# SteinerVCF.net
KiCad netlist of a schematic drawn in EAGLE
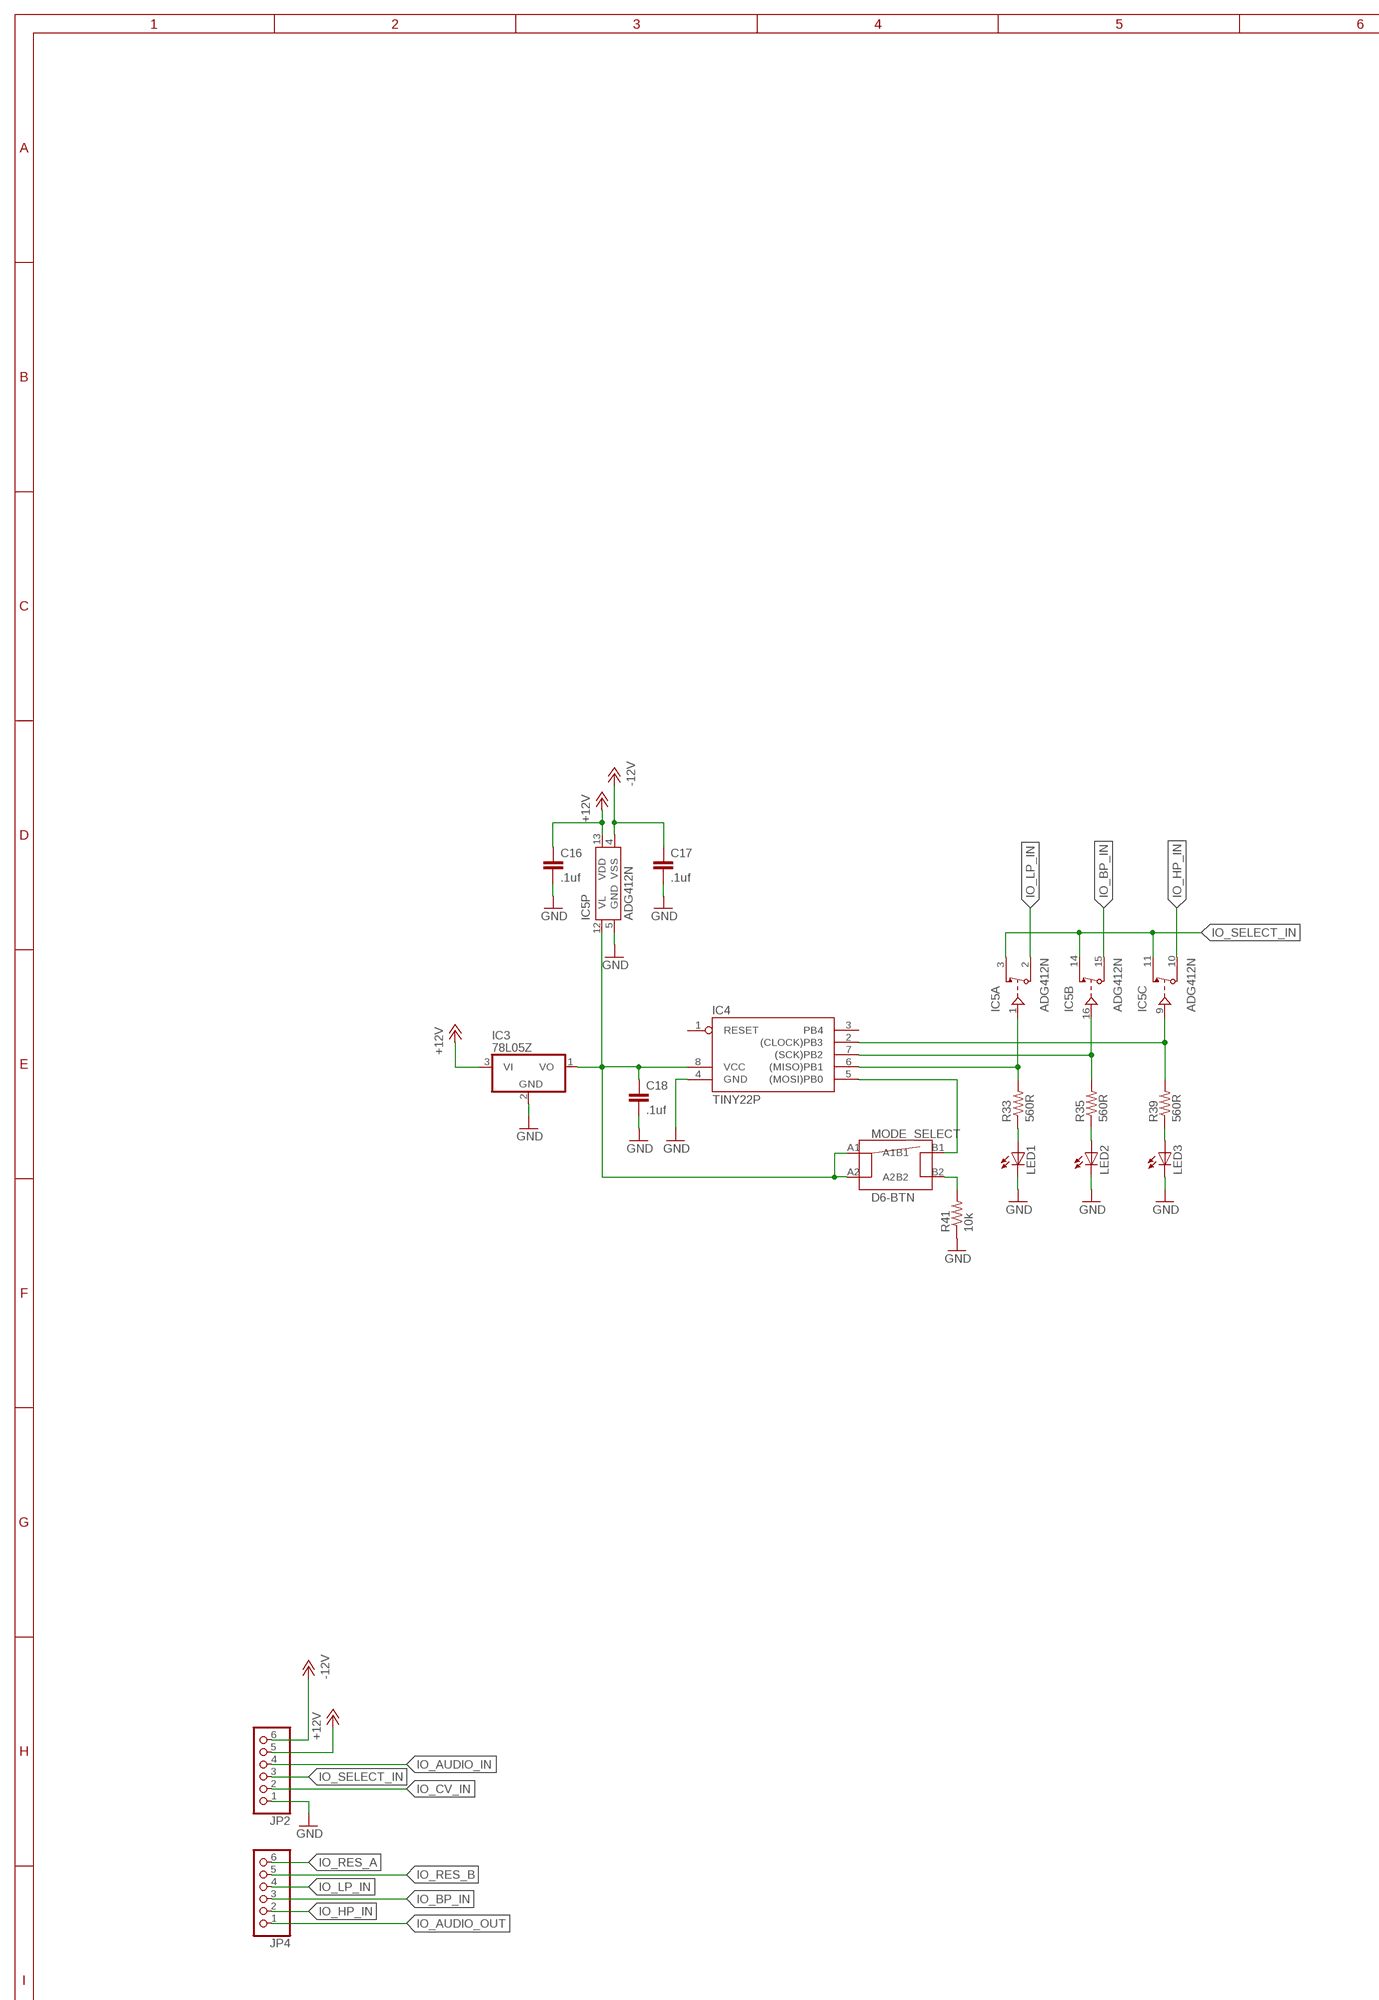
[diagram p0: schematic, sheet 1, part 1 of 2]
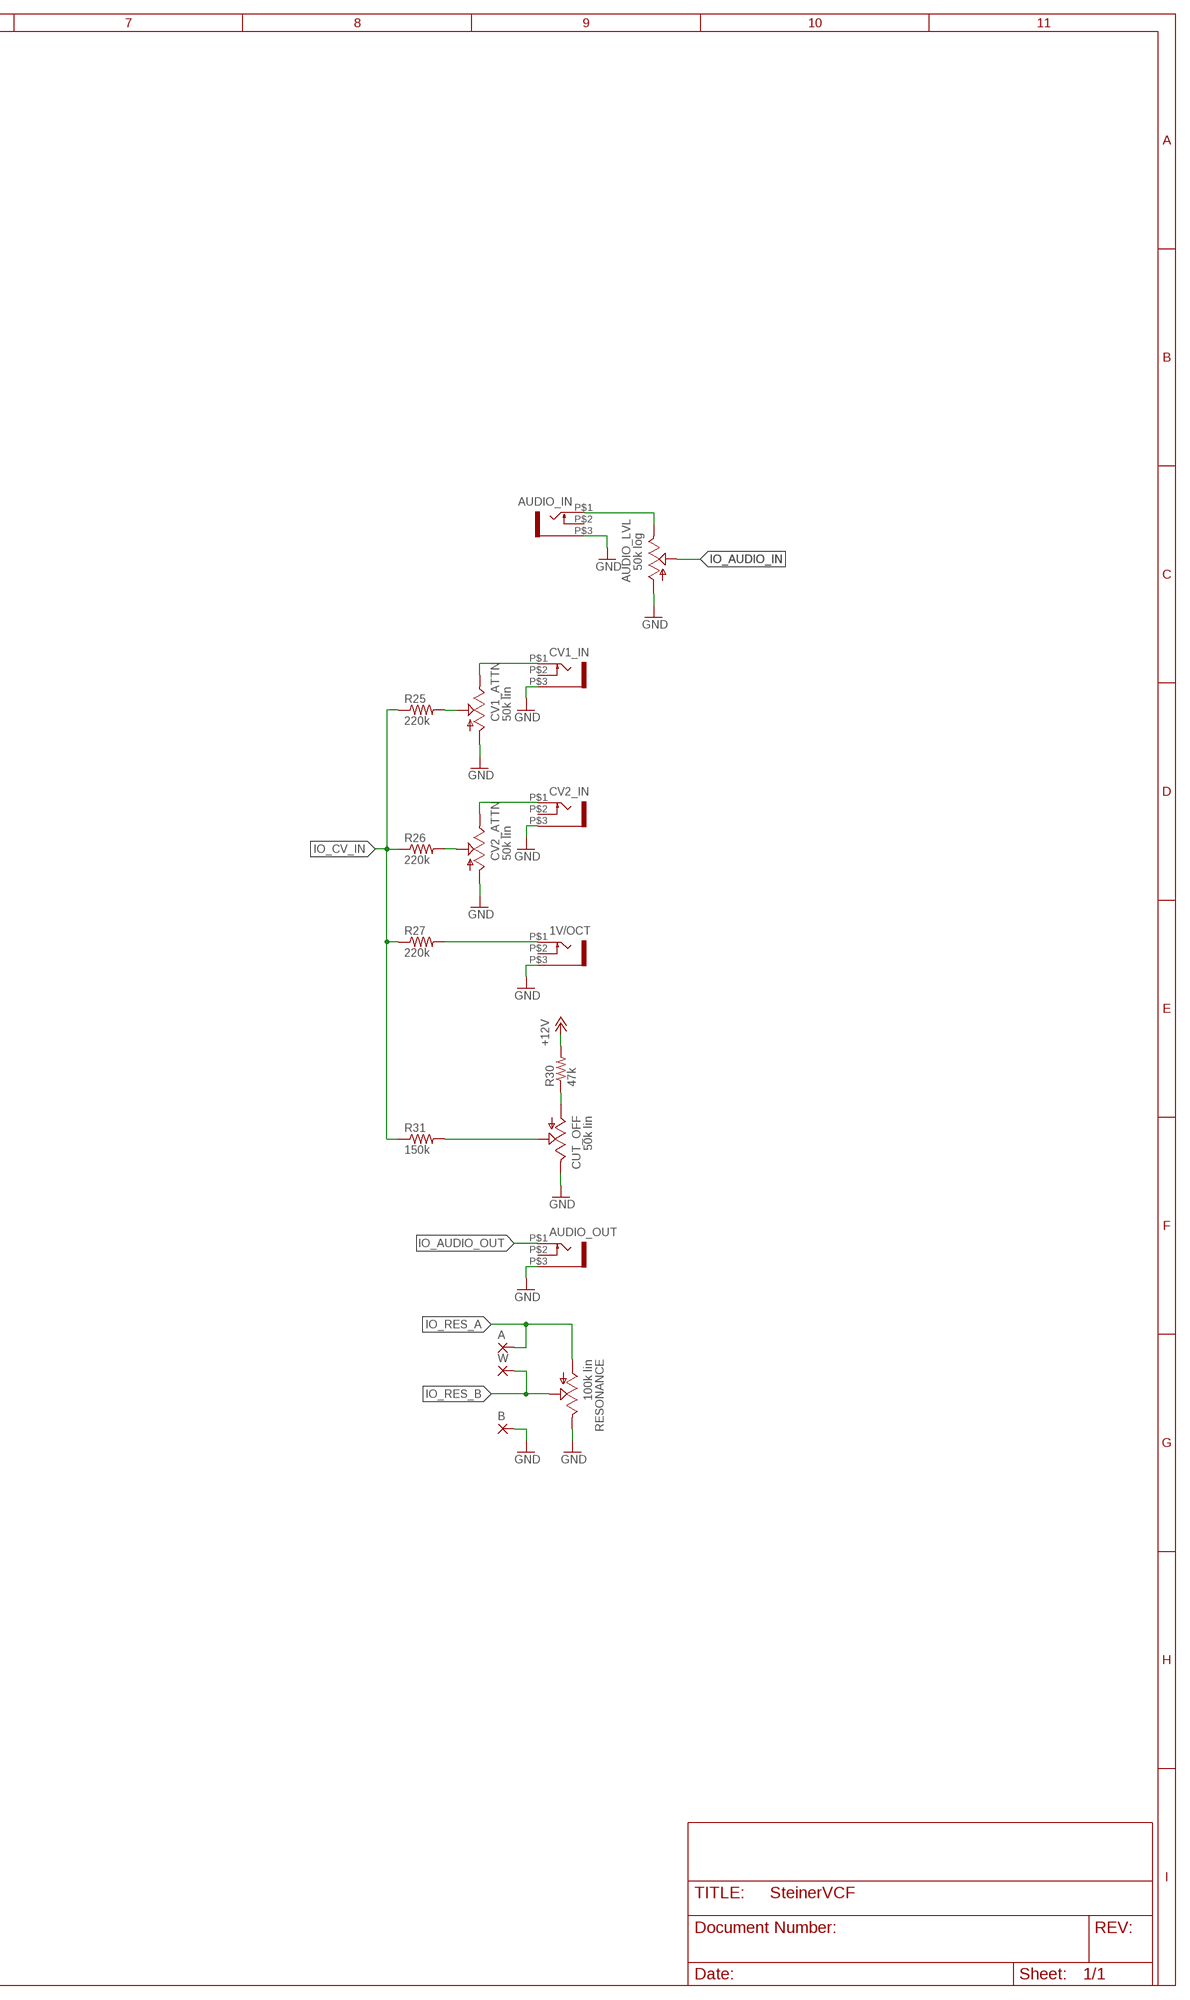
[diagram p1: schematic, sheet 1, part 2 of 2]

(export (version "E")
  (design (tool "Eeschema 10.0.6"))
  (components
    (comp (ref "1V/OCT")
      (value "WQP-PJ301M-12_JACK")
      (footprint "eagle-import:WQP-PJ301M-12_JACK")
      (libsource (lib "eagle-import") (part "WQP-PJ301M-12_JACK"))
    )
    (comp (ref "A")
      (value "2,15/1,0")
      (footprint "eagle-import:2,15_1,0")
      (libsource (lib "eagle-import") (part "2,15/1,0"))
    )
    (comp (ref "AUDIO_IN")
      (value "WQP-PJ301M-12_JACK")
      (footprint "eagle-import:WQP-PJ301M-12_JACK")
      (libsource (lib "eagle-import") (part "WQP-PJ301M-12_JACK"))
    )
    (comp (ref "AUDIO_LVL")
      (value "50k log")
      (footprint "eagle-import:EVUF")
      (libsource (lib "eagle-import") (part "ALPHA-9MMA"))
    )
    (comp (ref "AUDIO_OUT")
      (value "WQP-PJ301M-12_JACK")
      (footprint "eagle-import:WQP-PJ301M-12_JACK")
      (libsource (lib "eagle-import") (part "WQP-PJ301M-12_JACK"))
    )
    (comp (ref "B")
      (value "2,15/1,0")
      (footprint "eagle-import:2,15_1,0")
      (libsource (lib "eagle-import") (part "2,15/1,0"))
    )
    (comp (ref "C16")
      (value ".1uf")
      (footprint "eagle-import:C050-024X044")
      (libsource (lib "eagle-import") (part "C-EU050-024X044"))
    )
    (comp (ref "C17")
      (value ".1uf")
      (footprint "eagle-import:C050-024X044")
      (libsource (lib "eagle-import") (part "C-EU050-024X044"))
    )
    (comp (ref "C18")
      (value ".1uf")
      (footprint "eagle-import:C050-024X044")
      (libsource (lib "eagle-import") (part "C-EU050-024X044"))
    )
    (comp (ref "CUT_OFF")
      (value "50k lin")
      (footprint "eagle-import:EVUF")
      (libsource (lib "eagle-import") (part "ALPHA-9MMA"))
    )
    (comp (ref "CV1_ATTN")
      (value "50k lin")
      (footprint "eagle-import:EVUF")
      (libsource (lib "eagle-import") (part "ALPHA-9MMA"))
    )
    (comp (ref "CV1_IN")
      (value "WQP-PJ301M-12_JACK")
      (footprint "eagle-import:WQP-PJ301M-12_JACK")
      (libsource (lib "eagle-import") (part "WQP-PJ301M-12_JACK"))
    )
    (comp (ref "CV2_ATTN")
      (value "50k lin")
      (footprint "eagle-import:EVUF")
      (libsource (lib "eagle-import") (part "ALPHA-9MMA"))
    )
    (comp (ref "CV2_IN")
      (value "WQP-PJ301M-12_JACK")
      (footprint "eagle-import:WQP-PJ301M-12_JACK")
      (libsource (lib "eagle-import") (part "WQP-PJ301M-12_JACK"))
    )
    (comp (ref "IC3")
      (value "78L05Z")
      (footprint "eagle-import:TO92")
      (libsource (lib "eagle-import") (part "78ZL05"))
    )
    (comp (ref "IC4")
      (value "TINY22P")
      (footprint "eagle-import:DIL08")
      (libsource (lib "eagle-import") (part "TINY22P"))
    )
    (comp (ref "IC5")
      (value "ADG412N")
      (footprint "eagle-import:DIL16")
      (fields (field (name "MF") "ALTERA CORPORATION") (field (name "MPN") "ADG412TQ"))
      (libsource (lib "eagle-import") (part "ADG412N"))
    )
    (comp (ref "JP2")
      (value "PINHD-1X6")
      (footprint "eagle-import:1X06")
      (libsource (lib "eagle-import") (part "PINHD-1X6"))
    )
    (comp (ref "JP4")
      (value "PINHD-1X6")
      (footprint "eagle-import:1X06")
      (libsource (lib "eagle-import") (part "PINHD-1X6"))
    )
    (comp (ref "LED1")
      (value "LED3MM")
      (footprint "eagle-import:LED3MM")
      (libsource (lib "eagle-import") (part "LED3MM"))
    )
    (comp (ref "LED2")
      (value "LED3MM")
      (footprint "eagle-import:LED3MM")
      (libsource (lib "eagle-import") (part "LED3MM"))
    )
    (comp (ref "LED3")
      (value "LED3MM")
      (footprint "eagle-import:LED3MM")
      (libsource (lib "eagle-import") (part "LED3MM"))
    )
    (comp (ref "MODE_SELECT")
      (value "D6-BTN")
      (footprint "eagle-import:D6-BTN")
      (libsource (lib "eagle-import") (part "D6-BTN"))
    )
    (comp (ref "R25")
      (value "220k")
      (footprint "eagle-import:0204_7")
      (libsource (lib "eagle-import") (part "R-US_0204/7"))
    )
    (comp (ref "R26")
      (value "220k")
      (footprint "eagle-import:0204_7")
      (libsource (lib "eagle-import") (part "R-US_0204/7"))
    )
    (comp (ref "R27")
      (value "220k")
      (footprint "eagle-import:0204_7")
      (libsource (lib "eagle-import") (part "R-US_0204/7"))
    )
    (comp (ref "R30")
      (value "47k")
      (footprint "eagle-import:0204_7")
      (libsource (lib "eagle-import") (part "R-US_0204/7"))
    )
    (comp (ref "R31")
      (value "150k")
      (footprint "eagle-import:0204_7")
      (libsource (lib "eagle-import") (part "R-US_0204/7"))
    )
    (comp (ref "R33")
      (value "560R")
      (footprint "eagle-import:0207_7")
      (libsource (lib "eagle-import") (part "R-US_0207/7"))
    )
    (comp (ref "R35")
      (value "560R")
      (footprint "eagle-import:0207_7")
      (libsource (lib "eagle-import") (part "R-US_0207/7"))
    )
    (comp (ref "R39")
      (value "560R")
      (footprint "eagle-import:0207_7")
      (libsource (lib "eagle-import") (part "R-US_0207/7"))
    )
    (comp (ref "R41")
      (value "10k")
      (footprint "eagle-import:0207_7")
      (libsource (lib "eagle-import") (part "R-US_0207/7"))
    )
    (comp (ref "RESONANCE")
      (value "100k lin")
      (footprint "eagle-import:EVUF")
      (libsource (lib "eagle-import") (part "ALPHA-9MMA"))
    )
    (comp (ref "W")
      (value "2,15/1,0")
      (footprint "eagle-import:2,15_1,0")
      (libsource (lib "eagle-import") (part "2,15/1,0"))
    )
  )
  (nets
    (net (code "1") (name "+12V") (class "Default")
      (node (ref "C16") (pin "1") (pinfunction "1_1") (pintype "passive"))
      (node (ref "IC3") (pin "3") (pinfunction "VI_3") (pintype "input"))
      (node (ref "IC5") (pin "13") (pinfunction "VDD_13") (pintype "power_in"))
      (node (ref "JP2") (pin "5") (pinfunction "5_5") (pintype "passive"))
      (node (ref "R30") (pin "2") (pinfunction "2_2") (pintype "passive"))
    )
    (net (code "2") (name "-12V") (class "Default")
      (node (ref "C17") (pin "1") (pinfunction "1_1") (pintype "passive"))
      (node (ref "IC5") (pin "4") (pinfunction "VSS_4") (pintype "power_in"))
      (node (ref "JP2") (pin "6") (pinfunction "6_6") (pintype "passive"))
    )
    (net (code "3") (name "GND") (class "Default")
      (node (ref "1V/OCT") (pin "P$3") (pinfunction "1_P$3") (pintype "passive"))
      (node (ref "AUDIO_IN") (pin "P$3") (pinfunction "1_P$3") (pintype "passive"))
      (node (ref "AUDIO_LVL") (pin "1") (pinfunction "A_1") (pintype "passive"))
      (node (ref "AUDIO_OUT") (pin "P$3") (pinfunction "1_P$3") (pintype "passive"))
      (node (ref "B") (pin "1") (pinfunction "P_1") (pintype "passive"))
      (node (ref "C16") (pin "2") (pinfunction "2_2") (pintype "passive"))
      (node (ref "C17") (pin "2") (pinfunction "2_2") (pintype "passive"))
      (node (ref "C18") (pin "2") (pinfunction "2_2") (pintype "passive"))
      (node (ref "CUT_OFF") (pin "3") (pinfunction "E_3") (pintype "passive"))
      (node (ref "CV1_ATTN") (pin "1") (pinfunction "A_1") (pintype "passive"))
      (node (ref "CV1_IN") (pin "P$3") (pinfunction "1_P$3") (pintype "passive"))
      (node (ref "CV2_ATTN") (pin "1") (pinfunction "A_1") (pintype "passive"))
      (node (ref "CV2_IN") (pin "P$3") (pinfunction "1_P$3") (pintype "passive"))
      (node (ref "IC3") (pin "2") (pinfunction "GND_2") (pintype "passive"))
      (node (ref "IC4") (pin "4") (pinfunction "GND_4") (pintype "power_in"))
      (node (ref "IC5") (pin "5") (pinfunction "GND_5") (pintype "power_in"))
      (node (ref "JP2") (pin "1") (pinfunction "1_1") (pintype "passive"))
      (node (ref "LED1") (pin "K") (pinfunction "C_K") (pintype "passive"))
      (node (ref "LED2") (pin "K") (pinfunction "C_K") (pintype "passive"))
      (node (ref "LED3") (pin "K") (pinfunction "C_K") (pintype "passive"))
      (node (ref "R41") (pin "1") (pinfunction "1_1") (pintype "passive"))
      (node (ref "RESONANCE") (pin "3") (pinfunction "E_3") (pintype "passive"))
    )
    (net (code "4") (name "IO_AUDIO_IN") (class "Default")
      (node (ref "AUDIO_LVL") (pin "2") (pinfunction "S_2") (pintype "passive"))
      (node (ref "JP2") (pin "4") (pinfunction "4_4") (pintype "passive"))
    )
    (net (code "5") (name "IO_AUDIO_OUT") (class "Default")
      (node (ref "AUDIO_OUT") (pin "P$1") (pinfunction "2_P$1") (pintype "passive"))
      (node (ref "JP4") (pin "1") (pinfunction "1_1") (pintype "passive"))
    )
    (net (code "6") (name "IO_BP_IN") (class "Default")
      (node (ref "IC5") (pin "15") (pinfunction "D_15") (pintype "passive"))
      (node (ref "JP4") (pin "3") (pinfunction "3_3") (pintype "passive"))
    )
    (net (code "7") (name "IO_CV_IN") (class "Default")
      (node (ref "JP2") (pin "2") (pinfunction "2_2") (pintype "passive"))
      (node (ref "R25") (pin "1") (pinfunction "1_1") (pintype "passive"))
      (node (ref "R26") (pin "1") (pinfunction "1_1") (pintype "passive"))
      (node (ref "R27") (pin "1") (pinfunction "1_1") (pintype "passive"))
      (node (ref "R31") (pin "1") (pinfunction "1_1") (pintype "passive"))
    )
    (net (code "8") (name "IO_HP_IN") (class "Default")
      (node (ref "IC5") (pin "10") (pinfunction "D_10") (pintype "passive"))
      (node (ref "JP4") (pin "2") (pinfunction "2_2") (pintype "passive"))
    )
    (net (code "9") (name "IO_LP_IN") (class "Default")
      (node (ref "IC5") (pin "2") (pinfunction "D_2") (pintype "passive"))
      (node (ref "JP4") (pin "4") (pinfunction "4_4") (pintype "passive"))
    )
    (net (code "10") (name "IO_RES_A") (class "Default")
      (node (ref "A") (pin "1") (pinfunction "P_1") (pintype "passive"))
      (node (ref "JP4") (pin "6") (pinfunction "6_6") (pintype "passive"))
      (node (ref "RESONANCE") (pin "1") (pinfunction "A_1") (pintype "passive"))
    )
    (net (code "11") (name "IO_RES_B") (class "Default")
      (node (ref "JP4") (pin "5") (pinfunction "5_5") (pintype "passive"))
      (node (ref "RESONANCE") (pin "2") (pinfunction "S_2") (pintype "passive"))
      (node (ref "W") (pin "1") (pinfunction "P_1") (pintype "passive"))
    )
    (net (code "12") (name "IO_SELECT_IN") (class "Default")
      (node (ref "IC5") (pin "11") (pinfunction "S_11") (pintype "passive"))
      (node (ref "IC5") (pin "14") (pinfunction "S_14") (pintype "passive"))
      (node (ref "IC5") (pin "3") (pinfunction "S_3") (pintype "passive"))
      (node (ref "JP2") (pin "3") (pinfunction "3_3") (pintype "passive"))
    )
    (net (code "13") (name "Net-(1V/OCT-2)") (class "Default")
      (node (ref "1V/OCT") (pin "P$1") (pinfunction "2_P$1") (pintype "passive"))
      (node (ref "R27") (pin "2") (pinfunction "2_2") (pintype "passive"))
    )
    (net (code "14") (name "Net-(AUDIO_IN-2)") (class "Default")
      (node (ref "AUDIO_IN") (pin "P$1") (pinfunction "2_P$1") (pintype "passive"))
      (node (ref "AUDIO_LVL") (pin "3") (pinfunction "E_3") (pintype "passive"))
    )
    (net (code "15") (name "Net-(CUT_OFF-A)") (class "Default")
      (node (ref "CUT_OFF") (pin "1") (pinfunction "A_1") (pintype "passive"))
      (node (ref "R30") (pin "1") (pinfunction "1_1") (pintype "passive"))
    )
    (net (code "16") (name "Net-(CUT_OFF-S)") (class "Default")
      (node (ref "CUT_OFF") (pin "2") (pinfunction "S_2") (pintype "passive"))
      (node (ref "R31") (pin "2") (pinfunction "2_2") (pintype "passive"))
    )
    (net (code "17") (name "Net-(CV1_ATTN-E)") (class "Default")
      (node (ref "CV1_ATTN") (pin "3") (pinfunction "E_3") (pintype "passive"))
      (node (ref "CV1_IN") (pin "P$1") (pinfunction "2_P$1") (pintype "passive"))
    )
    (net (code "18") (name "Net-(CV1_ATTN-S)") (class "Default")
      (node (ref "CV1_ATTN") (pin "2") (pinfunction "S_2") (pintype "passive"))
      (node (ref "R25") (pin "2") (pinfunction "2_2") (pintype "passive"))
    )
    (net (code "19") (name "Net-(CV2_ATTN-E)") (class "Default")
      (node (ref "CV2_ATTN") (pin "3") (pinfunction "E_3") (pintype "passive"))
      (node (ref "CV2_IN") (pin "P$1") (pinfunction "2_P$1") (pintype "passive"))
    )
    (net (code "20") (name "Net-(CV2_ATTN-S)") (class "Default")
      (node (ref "CV2_ATTN") (pin "2") (pinfunction "S_2") (pintype "passive"))
      (node (ref "R26") (pin "2") (pinfunction "2_2") (pintype "passive"))
    )
    (net (code "21") (name "Net-(IC3-VO)") (class "Default")
      (node (ref "C18") (pin "1") (pinfunction "1_1") (pintype "passive"))
      (node (ref "IC3") (pin "1") (pinfunction "VO_1") (pintype "passive"))
      (node (ref "IC4") (pin "8") (pinfunction "VCC_8") (pintype "power_in"))
      (node (ref "IC5") (pin "12") (pinfunction "VL_12") (pintype "power_in"))
      (node (ref "MODE_SELECT") (pin "A1") (pinfunction "A1_A1") (pintype "bidirectional"))
      (node (ref "MODE_SELECT") (pin "A2") (pinfunction "A2_A2") (pintype "bidirectional"))
    )
    (net (code "22") (name "Net-(IC4-(CLOCK)PB3)") (class "Default")
      (node (ref "IC4") (pin "2") (pinfunction "(CLOCK)PB3_2") (pintype "bidirectional"))
      (node (ref "IC5") (pin "9") (pinfunction "IN_9") (pintype "input"))
      (node (ref "R39") (pin "2") (pinfunction "2_2") (pintype "passive"))
    )
    (net (code "23") (name "Net-(IC4-(MISO)PB1)") (class "Default")
      (node (ref "IC4") (pin "6") (pinfunction "(MISO)PB1_6") (pintype "bidirectional"))
      (node (ref "IC5") (pin "1") (pinfunction "IN_1") (pintype "input"))
      (node (ref "R33") (pin "2") (pinfunction "2_2") (pintype "passive"))
    )
    (net (code "24") (name "Net-(IC4-(MOSI)PB0)") (class "Default")
      (node (ref "IC4") (pin "5") (pinfunction "(MOSI)PB0_5") (pintype "bidirectional"))
      (node (ref "MODE_SELECT") (pin "B1") (pinfunction "B1_B1") (pintype "bidirectional"))
    )
    (net (code "25") (name "Net-(IC4-(SCK)PB2)") (class "Default")
      (node (ref "IC4") (pin "7") (pinfunction "(SCK)PB2_7") (pintype "bidirectional"))
      (node (ref "IC5") (pin "16") (pinfunction "IN_16") (pintype "input"))
      (node (ref "R35") (pin "2") (pinfunction "2_2") (pintype "passive"))
    )
    (net (code "26") (name "Net-(LED1-PadA)") (class "Default")
      (node (ref "LED1") (pin "A") (pinfunction "A_A") (pintype "passive"))
      (node (ref "R33") (pin "1") (pinfunction "1_1") (pintype "passive"))
    )
    (net (code "27") (name "Net-(LED2-PadA)") (class "Default")
      (node (ref "LED2") (pin "A") (pinfunction "A_A") (pintype "passive"))
      (node (ref "R35") (pin "1") (pinfunction "1_1") (pintype "passive"))
    )
    (net (code "28") (name "Net-(LED3-PadA)") (class "Default")
      (node (ref "LED3") (pin "A") (pinfunction "A_A") (pintype "passive"))
      (node (ref "R39") (pin "1") (pinfunction "1_1") (pintype "passive"))
    )
    (net (code "29") (name "Net-(MODE_SELECT-PadB2)") (class "Default")
      (node (ref "MODE_SELECT") (pin "B2") (pinfunction "B2_B2") (pintype "bidirectional"))
      (node (ref "R41") (pin "2") (pinfunction "2_2") (pintype "passive"))
    )
    (net (code "30") (name "unconnected-(1V/OCT-3-PadP$2)") (class "Default")
      (node (ref "1V/OCT") (pin "P$2") (pinfunction "3_P$2") (pintype "passive"))
    )
    (net (code "31") (name "unconnected-(AUDIO_IN-3-PadP$2)") (class "Default")
      (node (ref "AUDIO_IN") (pin "P$2") (pinfunction "3_P$2") (pintype "passive"))
    )
    (net (code "32") (name "unconnected-(AUDIO_OUT-3-PadP$2)") (class "Default")
      (node (ref "AUDIO_OUT") (pin "P$2") (pinfunction "3_P$2") (pintype "passive"))
    )
    (net (code "33") (name "unconnected-(CV1_IN-3-PadP$2)") (class "Default")
      (node (ref "CV1_IN") (pin "P$2") (pinfunction "3_P$2") (pintype "passive"))
    )
    (net (code "34") (name "unconnected-(CV2_IN-3-PadP$2)") (class "Default")
      (node (ref "CV2_IN") (pin "P$2") (pinfunction "3_P$2") (pintype "passive"))
    )
    (net (code "35") (name "unconnected-(IC4-PB4-Pad3)") (class "Default")
      (node (ref "IC4") (pin "3") (pinfunction "PB4_3") (pintype "bidirectional"))
    )
    (net (code "36") (name "unconnected-(IC4-RESET-Pad1)") (class "Default")
      (node (ref "IC4") (pin "1") (pinfunction "RESET_1") (pintype "input"))
    )
  )
)
